# Sheet1.net
KiCad netlist of a schematic drawn in Altium Designer
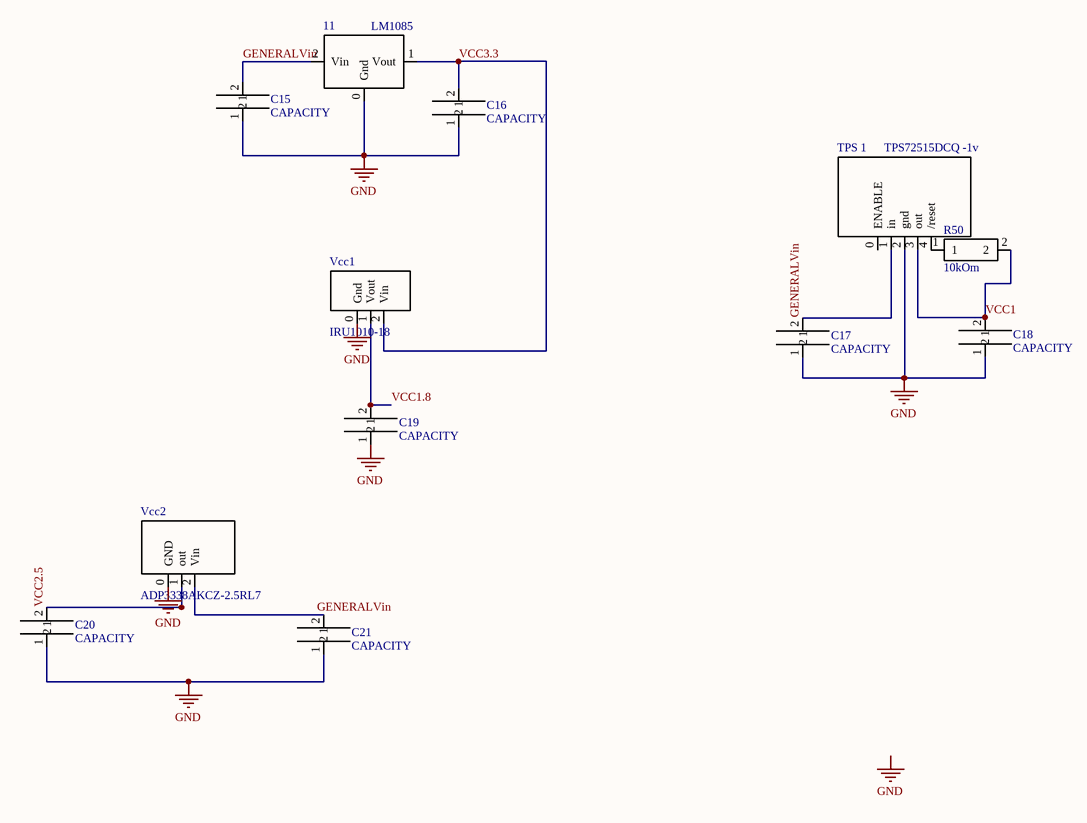
[diagram p0: Sheet1.SchDoc]

(export (version "E")
  (design (tool "Eeschema 10.0.6"))
  (components
    (comp (ref "11")
      (value "LM1085")
      (footprint "PcbLib1:LM1085")
      (libsource (lib "Library") (part "LM1085"))
    )
    (comp (ref "C15")
      (value "CAPACITY")
      (footprint "PcbLib1:R0805")
      (libsource (lib "Library") (part "CAPACITY"))
    )
    (comp (ref "C16")
      (value "CAPACITY")
      (footprint "PcbLib1:R0805")
      (libsource (lib "Library") (part "CAPACITY"))
    )
    (comp (ref "C17")
      (value "CAPACITY")
      (footprint "PcbLib1:R0805")
      (libsource (lib "Library") (part "CAPACITY"))
    )
    (comp (ref "C18")
      (value "CAPACITY")
      (footprint "PcbLib1:R0805")
      (libsource (lib "Library") (part "CAPACITY"))
    )
    (comp (ref "C19")
      (value "CAPACITY")
      (footprint "PcbLib1:R0805")
      (libsource (lib "Library") (part "CAPACITY"))
    )
    (comp (ref "C20")
      (value "CAPACITY")
      (footprint "PcbLib1:R0805")
      (libsource (lib "Library") (part "CAPACITY"))
    )
    (comp (ref "C21")
      (value "CAPACITY")
      (footprint "PcbLib1:R0805")
      (libsource (lib "Library") (part "CAPACITY"))
    )
    (comp (ref "R50") (value "10kOm") (footprint "PcbLib1:R0805") (libsource (lib "Library") (part "R0805")))
    (comp (ref "TPS 1")
      (value "TPS72515DCQ -1v")
      (footprint "PcbLib1:SOT223-5")
      (libsource (lib "Library") (part "TPS72515DCQ -1v"))
    )
    (comp (ref "Vcc1")
      (value "IRU1010-18")
      (footprint "PcbLib1:IRU1010-18")
      (libsource (lib "Library") (part "IRU1010-18"))
    )
    (comp (ref "Vcc2")
      (value "ADP3338AKCZ-2.5RL7")
      (footprint "PcbLib1:sot223")
      (libsource (lib "Library") (part "ADP3338AKCZ-2.5RL7"))
    )
  )
  (nets
    (net (code "1") (name "/GENERALVin") (class "Default")
      (node (ref "11") (pin "2") (pinfunction "Vin_2") (pintype "passive"))
      (node (ref "C15") (pin "2") (pinfunction "2_2") (pintype "passive"))
      (node (ref "C17") (pin "2") (pinfunction "2_2") (pintype "passive"))
      (node (ref "C21") (pin "2") (pinfunction "2_2") (pintype "passive"))
      (node (ref "TPS 1") (pin "1") (pinfunction "in_1") (pintype "passive"))
      (node (ref "Vcc2") (pin "2") (pinfunction "Vin_2") (pintype "passive"))
    )
    (net (code "2") (name "/VCC1") (class "Default")
      (node (ref "C18") (pin "2") (pinfunction "2_2") (pintype "passive"))
      (node (ref "R50") (pin "2") (pinfunction "2_2") (pintype "passive"))
      (node (ref "TPS 1") (pin "3") (pinfunction "out_3") (pintype "passive"))
    )
    (net (code "3") (name "/VCC1.8") (class "Default")
      (node (ref "C19") (pin "2") (pinfunction "2_2") (pintype "passive"))
      (node (ref "Vcc1") (pin "1") (pinfunction "Vout_1") (pintype "passive"))
    )
    (net (code "4") (name "/VCC2.5") (class "Default")
      (node (ref "C20") (pin "2") (pinfunction "2_2") (pintype "passive"))
      (node (ref "Vcc2") (pin "1") (pinfunction "out_1") (pintype "passive"))
    )
    (net (code "5") (name "/VCC3.3") (class "Default")
      (node (ref "11") (pin "1") (pinfunction "Vout_1") (pintype "passive"))
      (node (ref "C16") (pin "2") (pinfunction "2_2") (pintype "passive"))
      (node (ref "Vcc1") (pin "2") (pinfunction "Vin_2") (pintype "passive"))
    )
    (net (code "6") (name "GND") (class "Default")
      (node (ref "11") (pin "0") (pinfunction "Gnd_0") (pintype "passive"))
      (node (ref "C15") (pin "1") (pinfunction "1_1") (pintype "passive"))
      (node (ref "C16") (pin "1") (pinfunction "1_1") (pintype "passive"))
      (node (ref "C17") (pin "1") (pinfunction "1_1") (pintype "passive"))
      (node (ref "C18") (pin "1") (pinfunction "1_1") (pintype "passive"))
      (node (ref "C19") (pin "1") (pinfunction "1_1") (pintype "passive"))
      (node (ref "C20") (pin "1") (pinfunction "1_1") (pintype "passive"))
      (node (ref "C21") (pin "1") (pinfunction "1_1") (pintype "passive"))
      (node (ref "TPS 1") (pin "2") (pinfunction "gnd_2") (pintype "passive"))
      (node (ref "Vcc1") (pin "0") (pinfunction "Gnd_0") (pintype "passive"))
      (node (ref "Vcc2") (pin "0") (pinfunction "GND_0") (pintype "passive"))
    )
    (net (code "7") (name "Net-(TPS 1-{slash}reset)") (class "Default")
      (node (ref "R50") (pin "1") (pinfunction "1_1") (pintype "passive"))
      (node (ref "TPS 1") (pin "4") (pinfunction "/reset_4") (pintype "passive"))
    )
    (net (code "8") (name "unconnected-(TPS 1-ENABLE-Pad0)") (class "Default")
      (node (ref "TPS 1") (pin "0") (pinfunction "ENABLE_0") (pintype "passive"))
    )
  )
)
